# 08_Motion.net
KiCad netlist of a schematic drawn in Altium Designer
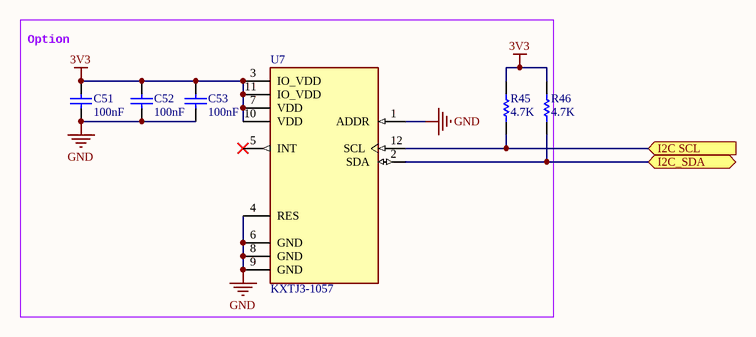
[diagram p0: 08 Motion.SchDoc]

(export (version "E")
  (design (tool "Eeschema 10.0.6"))
  (components
    (comp (ref "C51")
      (value "100nF")
      (footprint "0603 - C")
      (description "CAP CER 100nF 50V C0G/NP0 0603 ±5%")
      (fields (field (name "MPN") "CL10C104JB8NNNC") (field (name "MFR") "SAMSUNG"))
      (libsource (lib "Library_Chip") (part "Cap 0603 100nF"))
    )
    (comp (ref "C52")
      (value "100nF")
      (footprint "0603 - C")
      (description "CAP CER 100nF 50V C0G/NP0 0603 ±5%")
      (fields (field (name "MPN") "CL10C104JB8NNNC") (field (name "MFR") "SAMSUNG"))
      (libsource (lib "Library_Chip") (part "Cap 0603 100nF"))
    )
    (comp (ref "C53")
      (value "100nF")
      (footprint "0603 - C")
      (description "CAP CER 100nF 50V C0G/NP0 0603 ±5%")
      (fields (field (name "MPN") "CL10C104JB8NNNC") (field (name "MFR") "SAMSUNG"))
      (libsource (lib "Library_Chip") (part "Cap 0603 100nF"))
    )
    (comp (ref "R45")
      (value "4.7K")
      (footprint "0603 - R")
      (description "RES SMD 4.7K OHM 1% 1/10W 0603")
      (fields (field (name "MFR") "Yageo") (field (name "MPN") "RC0603FR-074K7L"))
      (libsource (lib "Library_Chip") (part "Res 0603 4.7K"))
    )
    (comp (ref "R46")
      (value "4.7K")
      (footprint "0603 - R")
      (description "RES SMD 4.7K OHM 1% 1/10W 0603")
      (fields (field (name "MFR") "Yageo") (field (name "MPN") "RC0603FR-074K7L"))
      (libsource (lib "Library_Chip") (part "Res 0603 4.7K"))
    )
    (comp (ref "U7")
      (value "KXTJ3-1057")
      (footprint "KXTJ3-1057")
      (description "ACCELEROMETER 2-16G I2C 12LGA")
      (fields (field (name "MFR") "Kionix Inc."))
      (libsource (lib "Library_IC") (part "KXTJ3-1057"))
    )
  )
  (nets
    (net (code "1") (name "/I2C SCL") (class "Default")
      (node (ref "R45") (pin "1") (pinfunction "1_1") (pintype "passive"))
      (node (ref "U7") (pin "12") (pinfunction "SCL_12") (pintype "input"))
    )
    (net (code "2") (name "/I2C_SDA") (class "Default")
      (node (ref "R46") (pin "1") (pinfunction "1_1") (pintype "passive"))
      (node (ref "U7") (pin "2") (pinfunction "SDA_2") (pintype "bidirectional"))
    )
    (net (code "3") (name "3V3") (class "Default")
      (node (ref "C51") (pin "2") (pinfunction "2_2") (pintype "passive"))
      (node (ref "C52") (pin "2") (pinfunction "2_2") (pintype "passive"))
      (node (ref "C53") (pin "2") (pinfunction "2_2") (pintype "passive"))
      (node (ref "R45") (pin "2") (pinfunction "2_2") (pintype "passive"))
      (node (ref "R46") (pin "2") (pinfunction "2_2") (pintype "passive"))
      (node (ref "U7") (pin "10") (pinfunction "VDD_10") (pintype "power_in"))
      (node (ref "U7") (pin "11") (pinfunction "IO_VDD_11") (pintype "power_in"))
      (node (ref "U7") (pin "3") (pinfunction "IO_VDD_3") (pintype "power_in"))
      (node (ref "U7") (pin "7") (pinfunction "VDD_7") (pintype "power_in"))
    )
    (net (code "4") (name "GND") (class "Default")
      (node (ref "C51") (pin "1") (pinfunction "1_1") (pintype "passive"))
      (node (ref "C52") (pin "1") (pinfunction "1_1") (pintype "passive"))
      (node (ref "C53") (pin "1") (pinfunction "1_1") (pintype "passive"))
      (node (ref "U7") (pin "1") (pinfunction "ADDR_1") (pintype "input"))
      (node (ref "U7") (pin "4") (pinfunction "RES_4") (pintype "passive"))
      (node (ref "U7") (pin "6") (pinfunction "GND_6") (pintype "power_in"))
      (node (ref "U7") (pin "8") (pinfunction "GND_8") (pintype "power_in"))
      (node (ref "U7") (pin "9") (pinfunction "GND_9") (pintype "power_in"))
    )
    (net (code "5") (name "unconnected-(U7-INT-Pad5)") (class "Default")
      (node (ref "U7") (pin "5") (pinfunction "INT_5") (pintype "output+no_connect"))
    )
  )
)
